# sb-sonata-debug.net
KiCad netlist of a schematic drawn in Altium Designer
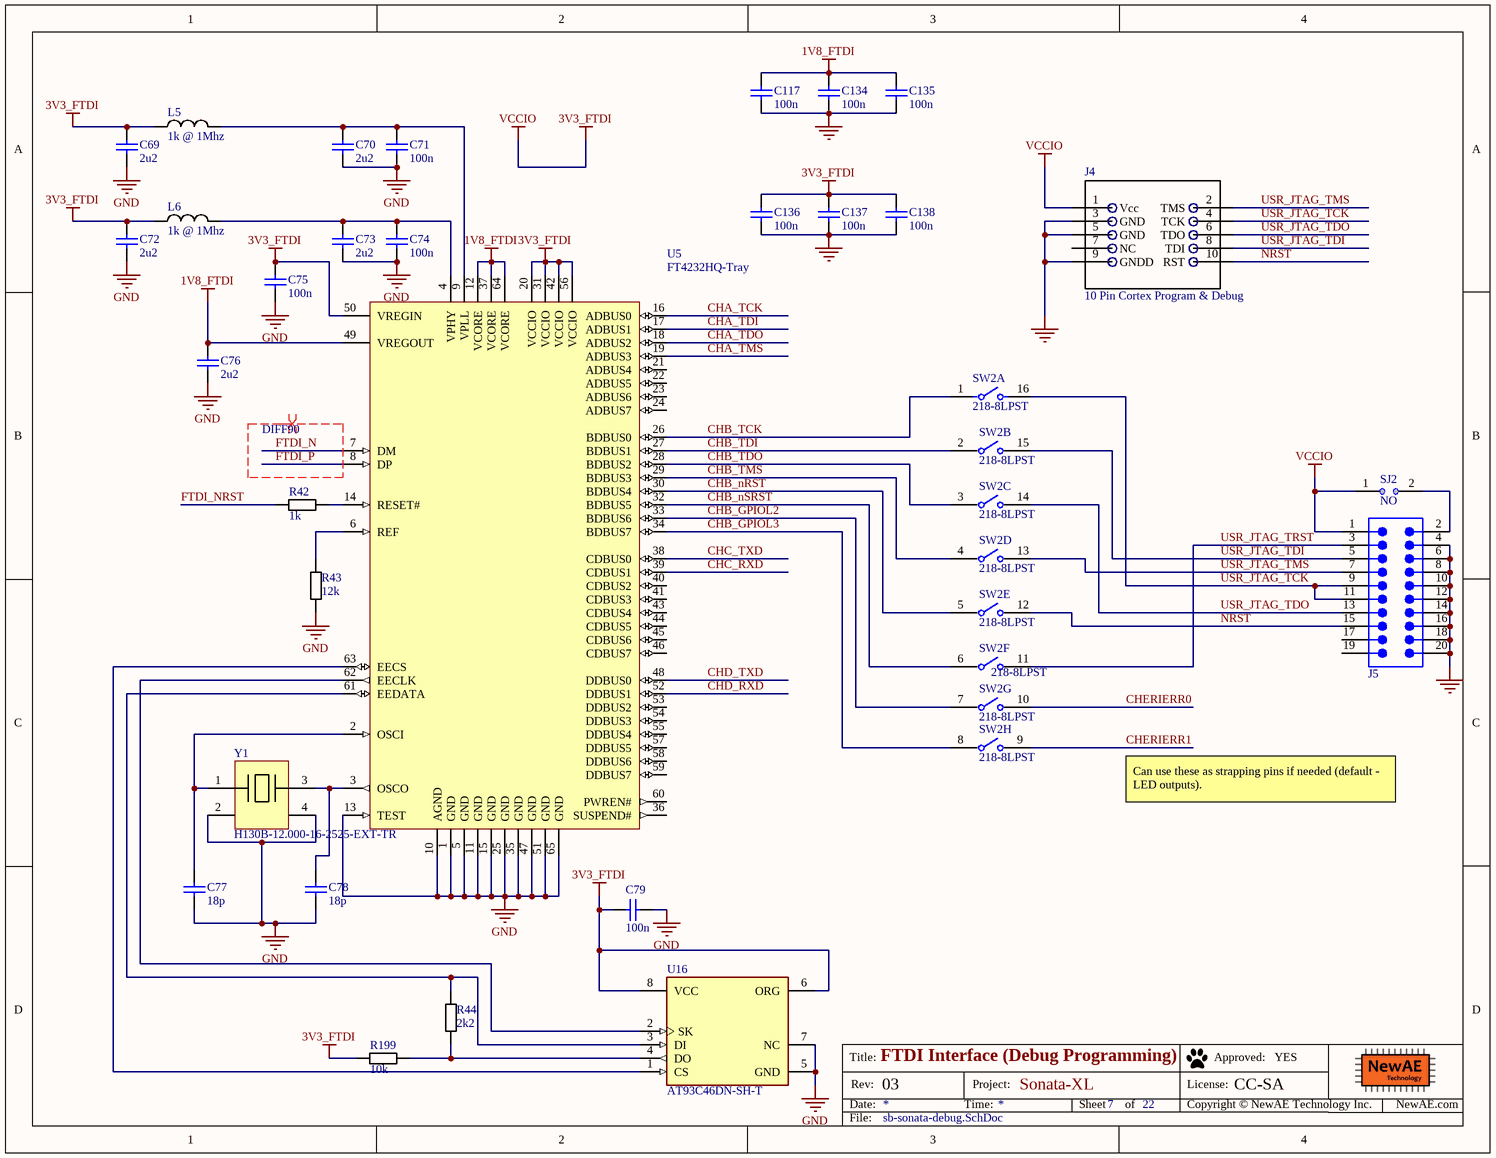
[diagram p0: sb-sonata-debug.SchDoc]

(export (version "E")
  (design (tool "Eeschema 10.0.6"))
  (components
    (comp (ref "C69")
      (value "2u2")
      (footprint "CAPC0603_M")
      (description "2u2, 0603")
      (fields (field (name "PART NUMBER") "CCHIP-2u2-0603"))
      (libsource (lib "NewAE_AltiumLib") (part "CAP"))
    )
    (comp (ref "C70")
      (value "2u2")
      (footprint "CAPC0603_M")
      (description "2u2, 0603")
      (fields (field (name "PART NUMBER") "CCHIP-2u2-0603"))
      (libsource (lib "NewAE_AltiumLib") (part "CAP"))
    )
    (comp (ref "C71")
      (value "100n")
      (footprint "CAPC0402_M")
      (description "100n, 0402")
      (fields (field (name "PART NUMBER") "CCHIP-100n-0402"))
      (libsource (lib "NewAE_AltiumLib") (part "CAP"))
    )
    (comp (ref "C72")
      (value "2u2")
      (footprint "CAPC0603_M")
      (description "2u2, 0603")
      (fields (field (name "PART NUMBER") "CCHIP-2u2-0603"))
      (libsource (lib "NewAE_AltiumLib") (part "CAP"))
    )
    (comp (ref "C73")
      (value "2u2")
      (footprint "CAPC0603_M")
      (description "2u2, 0603")
      (fields (field (name "PART NUMBER") "CCHIP-2u2-0603"))
      (libsource (lib "NewAE_AltiumLib") (part "CAP"))
    )
    (comp (ref "C74")
      (value "100n")
      (footprint "CAPC0402_M")
      (description "100n, 0402")
      (fields (field (name "PART NUMBER") "CCHIP-100n-0402"))
      (libsource (lib "NewAE_AltiumLib") (part "CAP"))
    )
    (comp (ref "C75")
      (value "100n")
      (footprint "CAPC0402_M")
      (description "100n, 0402")
      (fields (field (name "PART NUMBER") "CCHIP-100n-0402"))
      (libsource (lib "NewAE_AltiumLib") (part "CAP"))
    )
    (comp (ref "C76")
      (value "2u2")
      (footprint "CAPC0603_M")
      (description "2u2, 0603")
      (fields (field (name "PART NUMBER") "CCHIP-2u2-0603"))
      (libsource (lib "NewAE_AltiumLib") (part "CAP"))
    )
    (comp (ref "C77")
      (value "18p")
      (footprint "CAPC0402_M")
      (description "18p, 0402")
      (fields (field (name "PART NUMBER") "CCHIP-18p-0402"))
      (libsource (lib "NewAE_AltiumLib") (part "CAP"))
    )
    (comp (ref "C78")
      (value "18p")
      (footprint "CAPC0402_M")
      (description "18p, 0402")
      (fields (field (name "PART NUMBER") "CCHIP-18p-0402"))
      (libsource (lib "NewAE_AltiumLib") (part "CAP"))
    )
    (comp (ref "C79")
      (value "100n")
      (footprint "CAPC0402_M")
      (description "100n, 0402")
      (fields (field (name "PART NUMBER") "CCHIP-100n-0402"))
      (libsource (lib "NewAE_AltiumLib") (part "CAP"))
    )
    (comp (ref "C117")
      (value "100n")
      (footprint "CAPC0402_M")
      (description "100n, 0402")
      (fields (field (name "PART NUMBER") "CCHIP-100n-0402"))
      (libsource (lib "NewAE_AltiumLib") (part "CAP"))
    )
    (comp (ref "C134")
      (value "100n")
      (footprint "CAPC0402_M")
      (description "100n, 0402")
      (fields (field (name "PART NUMBER") "CCHIP-100n-0402"))
      (libsource (lib "NewAE_AltiumLib") (part "CAP"))
    )
    (comp (ref "C135")
      (value "100n")
      (footprint "CAPC0402_M")
      (description "100n, 0402")
      (fields (field (name "PART NUMBER") "CCHIP-100n-0402"))
      (libsource (lib "NewAE_AltiumLib") (part "CAP"))
    )
    (comp (ref "C136")
      (value "100n")
      (footprint "CAPC0402_M")
      (description "100n, 0402")
      (fields (field (name "PART NUMBER") "CCHIP-100n-0402"))
      (libsource (lib "NewAE_AltiumLib") (part "CAP"))
    )
    (comp (ref "C137")
      (value "100n")
      (footprint "CAPC0402_M")
      (description "100n, 0402")
      (fields (field (name "PART NUMBER") "CCHIP-100n-0402"))
      (libsource (lib "NewAE_AltiumLib") (part "CAP"))
    )
    (comp (ref "C138")
      (value "100n")
      (footprint "CAPC0402_M")
      (description "100n, 0402")
      (fields (field (name "PART NUMBER") "CCHIP-100n-0402"))
      (libsource (lib "NewAE_AltiumLib") (part "CAP"))
    )
    (comp (ref "J4")
      (value "10 Pin Cortex Program & Debug")
      (footprint "0.5mm_SMD_Header_5x2")
      (description "10 Pin Cortex Program & Debug 0.5mm pitch")
      (fields (field (name "PART NUMBER") "Cortex_Debug_Header_10Pin"))
      (libsource (lib "NewAE_AltiumLib") (part "Cortex_Debug_Header_10Pin"))
    )
    (comp (ref "J5")
      (value "61232020621")
      (footprint "61232020621")
      (description "WR-BHD Male Box Header, SMT Straight, pitch 2.54mm, 2 row, 20 pin")
      (fields (field (name "MANUFACTURER") "Wurth Elektronik"))
      (libsource (lib "Altium_WR-BHD_rev22c") (part "61232020621"))
    )
    (comp (ref "L5")
      (value "1k @ 1Mhz")
      (footprint "IND_0603")
      (description "Ferrite Beads HI CUR CHIP BD 0603 1000OHMS 25%")
      (fields (field (name "PART NUMBER") "FBCHIP-1k-0603"))
      (libsource (lib "NewAE_AltiumLib") (part "IND"))
    )
    (comp (ref "L6")
      (value "1k @ 1Mhz")
      (footprint "IND_0603")
      (description "Ferrite Beads HI CUR CHIP BD 0603 1000OHMS 25%")
      (fields (field (name "PART NUMBER") "FBCHIP-1k-0603"))
      (libsource (lib "NewAE_AltiumLib") (part "IND"))
    )
    (comp (ref "R42")
      (value "1k")
      (footprint "RESC1005X40N")
      (description "1k res, 0402, 1%, 1/16W")
      (fields (field (name "PART NUMBER") "RCHIP-1K-0402") (field (name "TOLERANCE") "1%"))
      (libsource (lib "") (part "RES-EU_1"))
    )
    (comp (ref "R43")
      (value "12k")
      (footprint "RESC1608X55N")
      (description "12k res, 0603, 1%, 1/10W")
      (fields (field (name "PART NUMBER") "RCHIP-12K-0603") (field (name "TOLERANCE") "1%"))
      (libsource (lib "NewAE_AltiumLib") (part "RES-EU"))
    )
    (comp (ref "R44")
      (value "2k2")
      (footprint "RESC1005X40N")
      (description "2k2 res, 0402, 1%, 1/16W")
      (fields (field (name "PART NUMBER") "RCHIP-2K2-0402") (field (name "TOLERANCE") "1%"))
      (libsource (lib "NewAE_AltiumLib") (part "RES-EU"))
    )
    (comp (ref "R199")
      (value "10k")
      (footprint "RESC1005X40N")
      (description "10k res, 0402, 1%, 1/16W")
      (fields (field (name "PART NUMBER") "RCHIP-10K-0402") (field (name "TOLERANCE") "1%"))
      (libsource (lib "") (part "RES-EU_2"))
    )
    (comp (ref "SJ2")
      (value "NO")
      (footprint "SJ_2S_NO")
      (description "Solder Jumper, NO")
      (fields (field (name "PART NUMBER") "SJ_2S_NO"))
      (libsource (lib "NewAE_AltiumLib") (part "SJ_2S_NO"))
    )
    (comp (ref "SW2")
      (value "218-8LPST")
      (footprint "FP-218-8LPST-MFG")
      (description "SWITCH SLIDE DIP SPST 25MA 24V")
      (libsource (lib "Altium Content Vault") (part "c442af63ff53b934e43635f80d8690e"))
    )
    (comp (ref "U5")
      (value "FT4232HQ-Tray")
      (footprint "QFN64_2_N")
      (description "Quad High Speed USB To Multipurpose UART/MPSSE IC, 64-pin QFN, Tray")
      (fields (field (name "MANUFACTURER") "FTDI"))
      (libsource (lib "Altium Content Vault") (part "COM-UART-FT4232H-QFN64"))
    )
    (comp (ref "U16")
      (value "AT93C46DN-SH-T")
      (footprint "FP-C04-057-SN-MFG")
      (description "IC EEPROM 1K SPI 2MHZ 8SOIC")
      (fields
        (field (name "MANUFACTURER") "Microchip")
        (field (name "OCTOPART") "https://octopart.com/at93c46dn-sh-t-microchip-77759177")
      )
      (libsource (lib "Altium Content Vault") (part "8bb9afc094b350e480db350c7247e52"))
    )
    (comp (ref "Y1")
      (value "H130B-12.000-16-2525-EXT-TR")
      (footprint "5x3.2MM XTAL")
      (description "12MHz ±25ppm Crystal 16pF 35 Ohms 4-SMD, No Lead")
      (fields (field (name "MANUFACTURER PART NUMBER") "H130B-12.000-16-2525-EXT-TR"))
      (libsource (lib "NewAE_AltiumLib") (part "H130B-12.000-16-2525-EXT-TR"))
    )
  )
  (nets
    (net (code "1") (name "/CHA_TCK") (class "Default")
      (node (ref "U5") (pin "16") (pinfunction "ADBUS0_16") (pintype "bidirectional"))
    )
    (net (code "2") (name "/CHA_TDI") (class "Default")
      (node (ref "U5") (pin "17") (pinfunction "ADBUS1_17") (pintype "bidirectional"))
    )
    (net (code "3") (name "/CHA_TDO") (class "Default")
      (node (ref "U5") (pin "18") (pinfunction "ADBUS2_18") (pintype "bidirectional"))
    )
    (net (code "4") (name "/CHA_TMS") (class "Default")
      (node (ref "U5") (pin "19") (pinfunction "ADBUS3_19") (pintype "bidirectional"))
    )
    (net (code "5") (name "/CHB_GPIOL2") (class "Default")
      (node (ref "SW2") (pin "7") (pinfunction "7_7") (pintype "passive"))
      (node (ref "U5") (pin "33") (pinfunction "BDBUS6_33") (pintype "bidirectional"))
    )
    (net (code "6") (name "/CHB_GPIOL3") (class "Default")
      (node (ref "SW2") (pin "8") (pinfunction "8_8") (pintype "passive"))
      (node (ref "U5") (pin "34") (pinfunction "BDBUS7_34") (pintype "bidirectional"))
    )
    (net (code "7") (name "/CHB_TCK") (class "Default")
      (node (ref "SW2") (pin "1") (pinfunction "1_1") (pintype "passive"))
      (node (ref "U5") (pin "26") (pinfunction "BDBUS0_26") (pintype "bidirectional"))
    )
    (net (code "8") (name "/CHB_TDI") (class "Default")
      (node (ref "SW2") (pin "2") (pinfunction "2_2") (pintype "passive"))
      (node (ref "U5") (pin "27") (pinfunction "BDBUS1_27") (pintype "bidirectional"))
    )
    (net (code "9") (name "/CHB_TDO") (class "Default")
      (node (ref "SW2") (pin "3") (pinfunction "3_3") (pintype "passive"))
      (node (ref "U5") (pin "28") (pinfunction "BDBUS2_28") (pintype "bidirectional"))
    )
    (net (code "10") (name "/CHB_TMS") (class "Default")
      (node (ref "SW2") (pin "4") (pinfunction "4_4") (pintype "passive"))
      (node (ref "U5") (pin "29") (pinfunction "BDBUS3_29") (pintype "bidirectional"))
    )
    (net (code "11") (name "/CHB_nRST") (class "Default")
      (node (ref "SW2") (pin "5") (pinfunction "5_5") (pintype "passive"))
      (node (ref "U5") (pin "30") (pinfunction "BDBUS4_30") (pintype "bidirectional"))
    )
    (net (code "12") (name "/CHB_nSRST") (class "Default")
      (node (ref "SW2") (pin "6") (pinfunction "6_6") (pintype "passive"))
      (node (ref "U5") (pin "32") (pinfunction "BDBUS5_32") (pintype "bidirectional"))
    )
    (net (code "13") (name "/CHC_RXD") (class "Default")
      (node (ref "U5") (pin "39") (pinfunction "CDBUS1_39") (pintype "bidirectional"))
    )
    (net (code "14") (name "/CHC_TXD") (class "Default")
      (node (ref "U5") (pin "38") (pinfunction "CDBUS0_38") (pintype "bidirectional"))
    )
    (net (code "15") (name "/CHD_RXD") (class "Default")
      (node (ref "U5") (pin "52") (pinfunction "DDBUS1_52") (pintype "bidirectional"))
    )
    (net (code "16") (name "/CHD_TXD") (class "Default")
      (node (ref "U5") (pin "48") (pinfunction "DDBUS0_48") (pintype "bidirectional"))
    )
    (net (code "17") (name "/CHERIERR0") (class "Default")
      (node (ref "SW2") (pin "10") (pinfunction "10_10") (pintype "passive"))
    )
    (net (code "18") (name "/CHERIERR1") (class "Default")
      (node (ref "SW2") (pin "9") (pinfunction "9_9") (pintype "passive"))
    )
    (net (code "19") (name "/FTDI_N") (class "Default")
      (node (ref "U5") (pin "7") (pinfunction "DM_7") (pintype "input"))
    )
    (net (code "20") (name "/FTDI_NRST") (class "Default")
      (node (ref "R42") (pin "2") (pinfunction "2_2") (pintype "passive"))
    )
    (net (code "21") (name "/FTDI_P") (class "Default")
      (node (ref "U5") (pin "8") (pinfunction "DP_8") (pintype "input"))
    )
    (net (code "22") (name "/NRST") (class "Default")
      (node (ref "J4") (pin "10") (pinfunction "RST_10") (pintype "passive"))
      (node (ref "J5") (pin "15") (pinfunction "15_15") (pintype "passive"))
      (node (ref "SW2") (pin "12") (pinfunction "12_12") (pintype "passive"))
    )
    (net (code "23") (name "/USR_JTAG_TCK") (class "Default")
      (node (ref "J4") (pin "4") (pinfunction "TCK_4") (pintype "passive"))
      (node (ref "J5") (pin "11") (pinfunction "11_11") (pintype "passive"))
      (node (ref "J5") (pin "9") (pinfunction "9_9") (pintype "passive"))
      (node (ref "SW2") (pin "16") (pinfunction "16_16") (pintype "passive"))
    )
    (net (code "24") (name "/USR_JTAG_TDI") (class "Default")
      (node (ref "J4") (pin "8") (pinfunction "TDI_8") (pintype "passive"))
      (node (ref "J5") (pin "5") (pinfunction "5_5") (pintype "passive"))
      (node (ref "SW2") (pin "15") (pinfunction "15_15") (pintype "passive"))
    )
    (net (code "25") (name "/USR_JTAG_TDO") (class "Default")
      (node (ref "J4") (pin "6") (pinfunction "TDO_6") (pintype "passive"))
      (node (ref "J5") (pin "13") (pinfunction "13_13") (pintype "passive"))
      (node (ref "SW2") (pin "14") (pinfunction "14_14") (pintype "passive"))
    )
    (net (code "26") (name "/USR_JTAG_TMS") (class "Default")
      (node (ref "J4") (pin "2") (pinfunction "TMS_2") (pintype "passive"))
      (node (ref "J5") (pin "7") (pinfunction "7_7") (pintype "passive"))
      (node (ref "SW2") (pin "13") (pinfunction "13_13") (pintype "passive"))
    )
    (net (code "27") (name "/USR_JTAG_TRST") (class "Default")
      (node (ref "J5") (pin "3") (pinfunction "3_3") (pintype "passive"))
      (node (ref "SW2") (pin "11") (pinfunction "11_11") (pintype "passive"))
    )
    (net (code "28") (name "1V8_FTDI") (class "Default")
      (node (ref "C117") (pin "1") (pinfunction "1_1") (pintype "passive"))
      (node (ref "C134") (pin "1") (pinfunction "1_1") (pintype "passive"))
      (node (ref "C135") (pin "1") (pinfunction "1_1") (pintype "passive"))
      (node (ref "C76") (pin "1") (pinfunction "1_1") (pintype "passive"))
      (node (ref "U5") (pin "12") (pinfunction "VCORE_12") (pintype "power_in"))
      (node (ref "U5") (pin "37") (pinfunction "VCORE_37") (pintype "power_in"))
      (node (ref "U5") (pin "49") (pinfunction "VREGOUT_49") (pintype "power_in"))
      (node (ref "U5") (pin "64") (pinfunction "VCORE_64") (pintype "power_in"))
    )
    (net (code "29") (name "3V3_FTDI") (class "Default")
      (node (ref "C136") (pin "1") (pinfunction "1_1") (pintype "passive"))
      (node (ref "C137") (pin "1") (pinfunction "1_1") (pintype "passive"))
      (node (ref "C138") (pin "1") (pinfunction "1_1") (pintype "passive"))
      (node (ref "C69") (pin "1") (pinfunction "1_1") (pintype "passive"))
      (node (ref "C72") (pin "1") (pinfunction "1_1") (pintype "passive"))
      (node (ref "C75") (pin "1") (pinfunction "1_1") (pintype "passive"))
      (node (ref "C79") (pin "1") (pinfunction "1_1") (pintype "passive"))
      (node (ref "J4") (pin "1") (pinfunction "Vcc_1") (pintype "passive"))
      (node (ref "J5") (pin "1") (pinfunction "1_1") (pintype "passive"))
      (node (ref "L5") (pin "1") (pinfunction "1_1") (pintype "passive"))
      (node (ref "L6") (pin "1") (pinfunction "1_1") (pintype "passive"))
      (node (ref "R199") (pin "1") (pinfunction "1_1") (pintype "passive"))
      (node (ref "SJ2") (pin "1") (pinfunction "1_1") (pintype "passive"))
      (node (ref "U16") (pin "6") (pinfunction "ORG_6") (pintype "passive"))
      (node (ref "U16") (pin "8") (pinfunction "VCC_8") (pintype "power_in"))
      (node (ref "U5") (pin "20") (pinfunction "VCCIO_20") (pintype "power_in"))
      (node (ref "U5") (pin "31") (pinfunction "VCCIO_31") (pintype "power_in"))
      (node (ref "U5") (pin "42") (pinfunction "VCCIO_42") (pintype "power_in"))
      (node (ref "U5") (pin "50") (pinfunction "VREGIN_50") (pintype "power_in"))
      (node (ref "U5") (pin "56") (pinfunction "VCCIO_56") (pintype "power_in"))
    )
    (net (code "30") (name "GND") (class "Default")
      (node (ref "C117") (pin "2") (pinfunction "2_2") (pintype "passive"))
      (node (ref "C134") (pin "2") (pinfunction "2_2") (pintype "passive"))
      (node (ref "C135") (pin "2") (pinfunction "2_2") (pintype "passive"))
      (node (ref "C136") (pin "2") (pinfunction "2_2") (pintype "passive"))
      (node (ref "C137") (pin "2") (pinfunction "2_2") (pintype "passive"))
      (node (ref "C138") (pin "2") (pinfunction "2_2") (pintype "passive"))
      (node (ref "C69") (pin "2") (pinfunction "2_2") (pintype "passive"))
      (node (ref "C70") (pin "2") (pinfunction "2_2") (pintype "passive"))
      (node (ref "C71") (pin "2") (pinfunction "2_2") (pintype "passive"))
      (node (ref "C72") (pin "2") (pinfunction "2_2") (pintype "passive"))
      (node (ref "C73") (pin "2") (pinfunction "2_2") (pintype "passive"))
      (node (ref "C74") (pin "2") (pinfunction "2_2") (pintype "passive"))
      (node (ref "C75") (pin "2") (pinfunction "2_2") (pintype "passive"))
      (node (ref "C76") (pin "2") (pinfunction "2_2") (pintype "passive"))
      (node (ref "C77") (pin "2") (pinfunction "2_2") (pintype "passive"))
      (node (ref "C78") (pin "2") (pinfunction "2_2") (pintype "passive"))
      (node (ref "C79") (pin "2") (pinfunction "2_2") (pintype "passive"))
      (node (ref "J4") (pin "3") (pinfunction "GND_3") (pintype "passive"))
      (node (ref "J4") (pin "5") (pinfunction "GND_5") (pintype "passive"))
      (node (ref "J4") (pin "9") (pinfunction "GNDD_9") (pintype "passive"))
      (node (ref "J5") (pin "10") (pinfunction "10_10") (pintype "passive"))
      (node (ref "J5") (pin "12") (pinfunction "12_12") (pintype "passive"))
      (node (ref "J5") (pin "14") (pinfunction "14_14") (pintype "passive"))
      (node (ref "J5") (pin "16") (pinfunction "16_16") (pintype "passive"))
      (node (ref "J5") (pin "18") (pinfunction "18_18") (pintype "passive"))
      (node (ref "J5") (pin "20") (pinfunction "20_20") (pintype "passive"))
      (node (ref "J5") (pin "4") (pinfunction "4_4") (pintype "passive"))
      (node (ref "J5") (pin "6") (pinfunction "6_6") (pintype "passive"))
      (node (ref "J5") (pin "8") (pinfunction "8_8") (pintype "passive"))
      (node (ref "R43") (pin "2") (pinfunction "2_2") (pintype "passive"))
      (node (ref "U16") (pin "5") (pinfunction "GND_5") (pintype "power_in"))
      (node (ref "U16") (pin "7") (pinfunction "NC_7") (pintype "passive"))
      (node (ref "U5") (pin "1") (pinfunction "GND_1") (pintype "power_in"))
      (node (ref "U5") (pin "10") (pinfunction "AGND_10") (pintype "power_in"))
      (node (ref "U5") (pin "11") (pinfunction "GND_11") (pintype "power_in"))
      (node (ref "U5") (pin "13") (pinfunction "TEST_13") (pintype "input"))
      (node (ref "U5") (pin "15") (pinfunction "GND_15") (pintype "power_in"))
      (node (ref "U5") (pin "25") (pinfunction "GND_25") (pintype "power_in"))
      (node (ref "U5") (pin "35") (pinfunction "GND_35") (pintype "power_in"))
      (node (ref "U5") (pin "47") (pinfunction "GND_47") (pintype "power_in"))
      (node (ref "U5") (pin "5") (pinfunction "GND_5") (pintype "power_in"))
      (node (ref "U5") (pin "51") (pinfunction "GND_51") (pintype "power_in"))
      (node (ref "U5") (pin "65") (pinfunction "GND_65") (pintype "power_in"))
      (node (ref "Y1") (pin "2") (pinfunction "2_2") (pintype "passive"))
      (node (ref "Y1") (pin "4") (pinfunction "4_4") (pintype "passive"))
    )
    (net (code "31") (name "Net-(J5-Pad2)") (class "Default")
      (node (ref "J5") (pin "2") (pinfunction "2_2") (pintype "passive"))
      (node (ref "SJ2") (pin "2") (pinfunction "2_2") (pintype "passive"))
    )
    (net (code "32") (name "Net-(U5-OSCI)") (class "Default")
      (node (ref "C77") (pin "1") (pinfunction "1_1") (pintype "passive"))
      (node (ref "U5") (pin "2") (pinfunction "OSCI_2") (pintype "input"))
      (node (ref "Y1") (pin "1") (pinfunction "1_1") (pintype "passive"))
    )
    (net (code "33") (name "Net-(U5-OSCO)") (class "Default")
      (node (ref "C78") (pin "1") (pinfunction "1_1") (pintype "passive"))
      (node (ref "U5") (pin "3") (pinfunction "OSCO_3") (pintype "output"))
      (node (ref "Y1") (pin "3") (pinfunction "3_3") (pintype "passive"))
    )
    (net (code "34") (name "Net-(U5-REF)") (class "Default")
      (node (ref "R43") (pin "1") (pinfunction "1_1") (pintype "passive"))
      (node (ref "U5") (pin "6") (pinfunction "REF_6") (pintype "input"))
    )
    (net (code "35") (name "Net-(U5-RESET#)") (class "Default")
      (node (ref "R42") (pin "1") (pinfunction "1_1") (pintype "passive"))
      (node (ref "U5") (pin "14") (pinfunction "RESET#_14") (pintype "input"))
    )
    (net (code "36") (name "Net-(U5-VPHY)") (class "Default")
      (node (ref "C73") (pin "1") (pinfunction "1_1") (pintype "passive"))
      (node (ref "C74") (pin "1") (pinfunction "1_1") (pintype "passive"))
      (node (ref "L6") (pin "2") (pinfunction "2_2") (pintype "passive"))
      (node (ref "U5") (pin "4") (pinfunction "VPHY_4") (pintype "power_in"))
    )
    (net (code "37") (name "Net-(U5-VPLL)") (class "Default")
      (node (ref "C70") (pin "1") (pinfunction "1_1") (pintype "passive"))
      (node (ref "C71") (pin "1") (pinfunction "1_1") (pintype "passive"))
      (node (ref "L5") (pin "2") (pinfunction "2_2") (pintype "passive"))
      (node (ref "U5") (pin "9") (pinfunction "VPLL_9") (pintype "power_in"))
    )
    (net (code "38") (name "Net-(U16-CS)") (class "Default")
      (node (ref "U16") (pin "1") (pinfunction "CS_1") (pintype "input"))
      (node (ref "U5") (pin "63") (pinfunction "EECS_63") (pintype "bidirectional"))
    )
    (net (code "39") (name "Net-(U16-DI)") (class "Default")
      (node (ref "R44") (pin "1") (pinfunction "1_1") (pintype "passive"))
      (node (ref "U16") (pin "3") (pinfunction "DI_3") (pintype "input"))
      (node (ref "U5") (pin "61") (pinfunction "EEDATA_61") (pintype "bidirectional"))
    )
    (net (code "40") (name "Net-(U16-DO)") (class "Default")
      (node (ref "R199") (pin "2") (pinfunction "2_2") (pintype "passive"))
      (node (ref "R44") (pin "2") (pinfunction "2_2") (pintype "passive"))
      (node (ref "U16") (pin "4") (pinfunction "DO_4") (pintype "output"))
    )
    (net (code "41") (name "Net-(U16-SK)") (class "Default")
      (node (ref "U16") (pin "2") (pinfunction "SK_2") (pintype "input"))
      (node (ref "U5") (pin "62") (pinfunction "EECLK_62") (pintype "output"))
    )
    (net (code "42") (name "unconnected-(J4-NC-Pad7)") (class "Default")
      (node (ref "J4") (pin "7") (pinfunction "NC_7") (pintype "passive"))
    )
    (net (code "43") (name "unconnected-(J5-Pad17)") (class "Default")
      (node (ref "J5") (pin "17") (pinfunction "17_17") (pintype "passive"))
    )
    (net (code "44") (name "unconnected-(J5-Pad19)") (class "Default")
      (node (ref "J5") (pin "19") (pinfunction "19_19") (pintype "passive"))
    )
    (net (code "45") (name "unconnected-(U5-ADBUS4-Pad21)") (class "Default")
      (node (ref "U5") (pin "21") (pinfunction "ADBUS4_21") (pintype "bidirectional"))
    )
    (net (code "46") (name "unconnected-(U5-ADBUS5-Pad22)") (class "Default")
      (node (ref "U5") (pin "22") (pinfunction "ADBUS5_22") (pintype "bidirectional"))
    )
    (net (code "47") (name "unconnected-(U5-ADBUS6-Pad23)") (class "Default")
      (node (ref "U5") (pin "23") (pinfunction "ADBUS6_23") (pintype "bidirectional"))
    )
    (net (code "48") (name "unconnected-(U5-ADBUS7-Pad24)") (class "Default")
      (node (ref "U5") (pin "24") (pinfunction "ADBUS7_24") (pintype "bidirectional"))
    )
    (net (code "49") (name "unconnected-(U5-CDBUS2-Pad40)") (class "Default")
      (node (ref "U5") (pin "40") (pinfunction "CDBUS2_40") (pintype "bidirectional"))
    )
    (net (code "50") (name "unconnected-(U5-CDBUS3-Pad41)") (class "Default")
      (node (ref "U5") (pin "41") (pinfunction "CDBUS3_41") (pintype "bidirectional"))
    )
    (net (code "51") (name "unconnected-(U5-CDBUS4-Pad43)") (class "Default")
      (node (ref "U5") (pin "43") (pinfunction "CDBUS4_43") (pintype "bidirectional"))
    )
    (net (code "52") (name "unconnected-(U5-CDBUS5-Pad44)") (class "Default")
      (node (ref "U5") (pin "44") (pinfunction "CDBUS5_44") (pintype "bidirectional"))
    )
    (net (code "53") (name "unconnected-(U5-CDBUS6-Pad45)") (class "Default")
      (node (ref "U5") (pin "45") (pinfunction "CDBUS6_45") (pintype "bidirectional"))
    )
    (net (code "54") (name "unconnected-(U5-CDBUS7-Pad46)") (class "Default")
      (node (ref "U5") (pin "46") (pinfunction "CDBUS7_46") (pintype "bidirectional"))
    )
    (net (code "55") (name "unconnected-(U5-DDBUS2-Pad53)") (class "Default")
      (node (ref "U5") (pin "53") (pinfunction "DDBUS2_53") (pintype "bidirectional"))
    )
    (net (code "56") (name "unconnected-(U5-DDBUS3-Pad54)") (class "Default")
      (node (ref "U5") (pin "54") (pinfunction "DDBUS3_54") (pintype "bidirectional"))
    )
    (net (code "57") (name "unconnected-(U5-DDBUS4-Pad55)") (class "Default")
      (node (ref "U5") (pin "55") (pinfunction "DDBUS4_55") (pintype "bidirectional"))
    )
    (net (code "58") (name "unconnected-(U5-DDBUS5-Pad57)") (class "Default")
      (node (ref "U5") (pin "57") (pinfunction "DDBUS5_57") (pintype "bidirectional"))
    )
    (net (code "59") (name "unconnected-(U5-DDBUS6-Pad58)") (class "Default")
      (node (ref "U5") (pin "58") (pinfunction "DDBUS6_58") (pintype "bidirectional"))
    )
    (net (code "60") (name "unconnected-(U5-DDBUS7-Pad59)") (class "Default")
      (node (ref "U5") (pin "59") (pinfunction "DDBUS7_59") (pintype "bidirectional"))
    )
    (net (code "61") (name "unconnected-(U5-PWREN#-Pad60)") (class "Default")
      (node (ref "U5") (pin "60") (pinfunction "PWREN#_60") (pintype "output"))
    )
    (net (code "62") (name "unconnected-(U5-SUSPEND#-Pad36)") (class "Default")
      (node (ref "U5") (pin "36") (pinfunction "SUSPEND#_36") (pintype "output"))
    )
  )
)
